# VoltageRegulator12V.net
KiCad netlist of a schematic drawn in Altium Designer
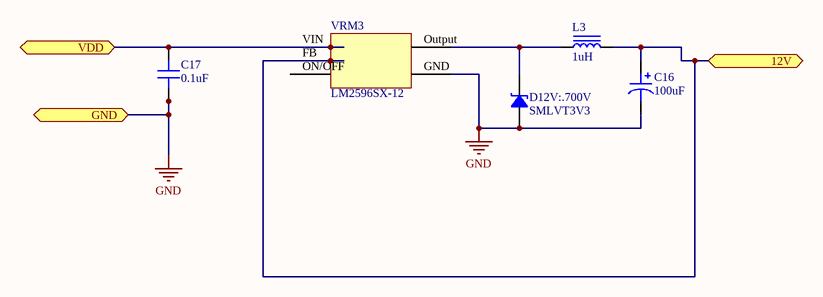
[diagram p0: VoltageRegulator12V.schdoc]

(export (version "E")
  (design (tool "Eeschema 10.0.6"))
  (components
    (comp (ref "C16")
      (value "100uF")
      (footprint "CAP ALUM 6.6MM")
      (description "CAP POLYMER 100UF 20% 16V SMD")
      (fields
        (field (name "PART NUMBER") "16SVPC100M")
        (field (name "MANUFACTURER") "Panasonic Electronic Components")
      )
      (libsource (lib "Celestial Library Database") (part "Polarised Capacitor"))
    )
    (comp (ref "C17")
      (value "0.1uF")
      (footprint "CAP 0402/1005")
      (description "CAP CER 0.1UF 16V X7R 0402")
      (fields
        (field (name "PART NUMBER") "C1005X7R1C104K050BC")
        (field (name "MANUFACTURER") "TDK Corporation")
      )
      (libsource (lib "Celestial Library Database") (part "Capacitor"))
    )
    (comp (ref "D12V:.700V")
      (value "SMLVT3V3")
      (footprint "ST DO214AA SMB")
      (description "TVS DIODE 3.3VWM 10.3VC SMB")
      (fields (field (name "MANUFACTURER") "STMicroelectronics"))
      (libsource (lib "Celestial Library Database") (part "Diode Zener"))
    )
    (comp (ref "L3")
      (value "1uH")
      (footprint "TDK VLS252010CX")
      (description "FIXED IND 1UH 2.29A 65 MOHM SMD")
      (fields (field (name "PART NUMBER") "VLS252010CX-1R0M") (field (name "MANUFACTURER") "TDK Corporation"))
      (libsource (lib "Celestial Library Database") (part "Inductor"))
    )
    (comp (ref "VRM3")
      (value "LM2596SX-12")
      (footprint "DPAK170P1418X200-6L")
      (libsource (lib "Schlib2") (part "LM2596SX-12"))
    )
  )
  (nets
    (net (code "1") (name "/12V") (class "Default")
      (node (ref "C16") (pin "1") (pinfunction "1_1") (pintype "passive"))
      (node (ref "L3") (pin "2") (pinfunction "2_2") (pintype "passive"))
      (node (ref "VRM3") (pin "FB") (pinfunction "*_FB") (pintype "passive"))
    )
    (net (code "2") (name "/VDD") (class "Default")
      (node (ref "C17") (pin "2") (pinfunction "2_2") (pintype "passive"))
      (node (ref "VRM3") (pin "VIN") (pinfunction "Vin_VIN") (pintype "passive"))
    )
    (net (code "3") (name "GND") (class "Default")
      (node (ref "C16") (pin "2") (pinfunction "2_2") (pintype "passive"))
      (node (ref "C17") (pin "1") (pinfunction "1_1") (pintype "passive"))
      (node (ref "D12V:.700V") (pin "1") (pinfunction "1_1") (pintype "passive"))
      (node (ref "VRM3") (pin "GND") (pinfunction "*_GND") (pintype "passive"))
    )
    (net (code "4") (name "Net-(D12V:.700V-Pad2)") (class "Default")
      (node (ref "D12V:.700V") (pin "2") (pinfunction "2_2") (pintype "passive"))
      (node (ref "L3") (pin "1") (pinfunction "1_1") (pintype "passive"))
      (node (ref "VRM3") (pin "Output") (pinfunction "*_Output") (pintype "passive"))
    )
    (net (code "5") (name "unconnected-(VRM3-*-PadON{slash}OFF)") (class "Default")
      (node (ref "VRM3") (pin "ON/OFF") (pinfunction "*_ON/OFF") (pintype "passive"))
    )
  )
)
